# 7_ZynTra-DDR3L_Modules.net
KiCad netlist of a schematic drawn in Altium Designer
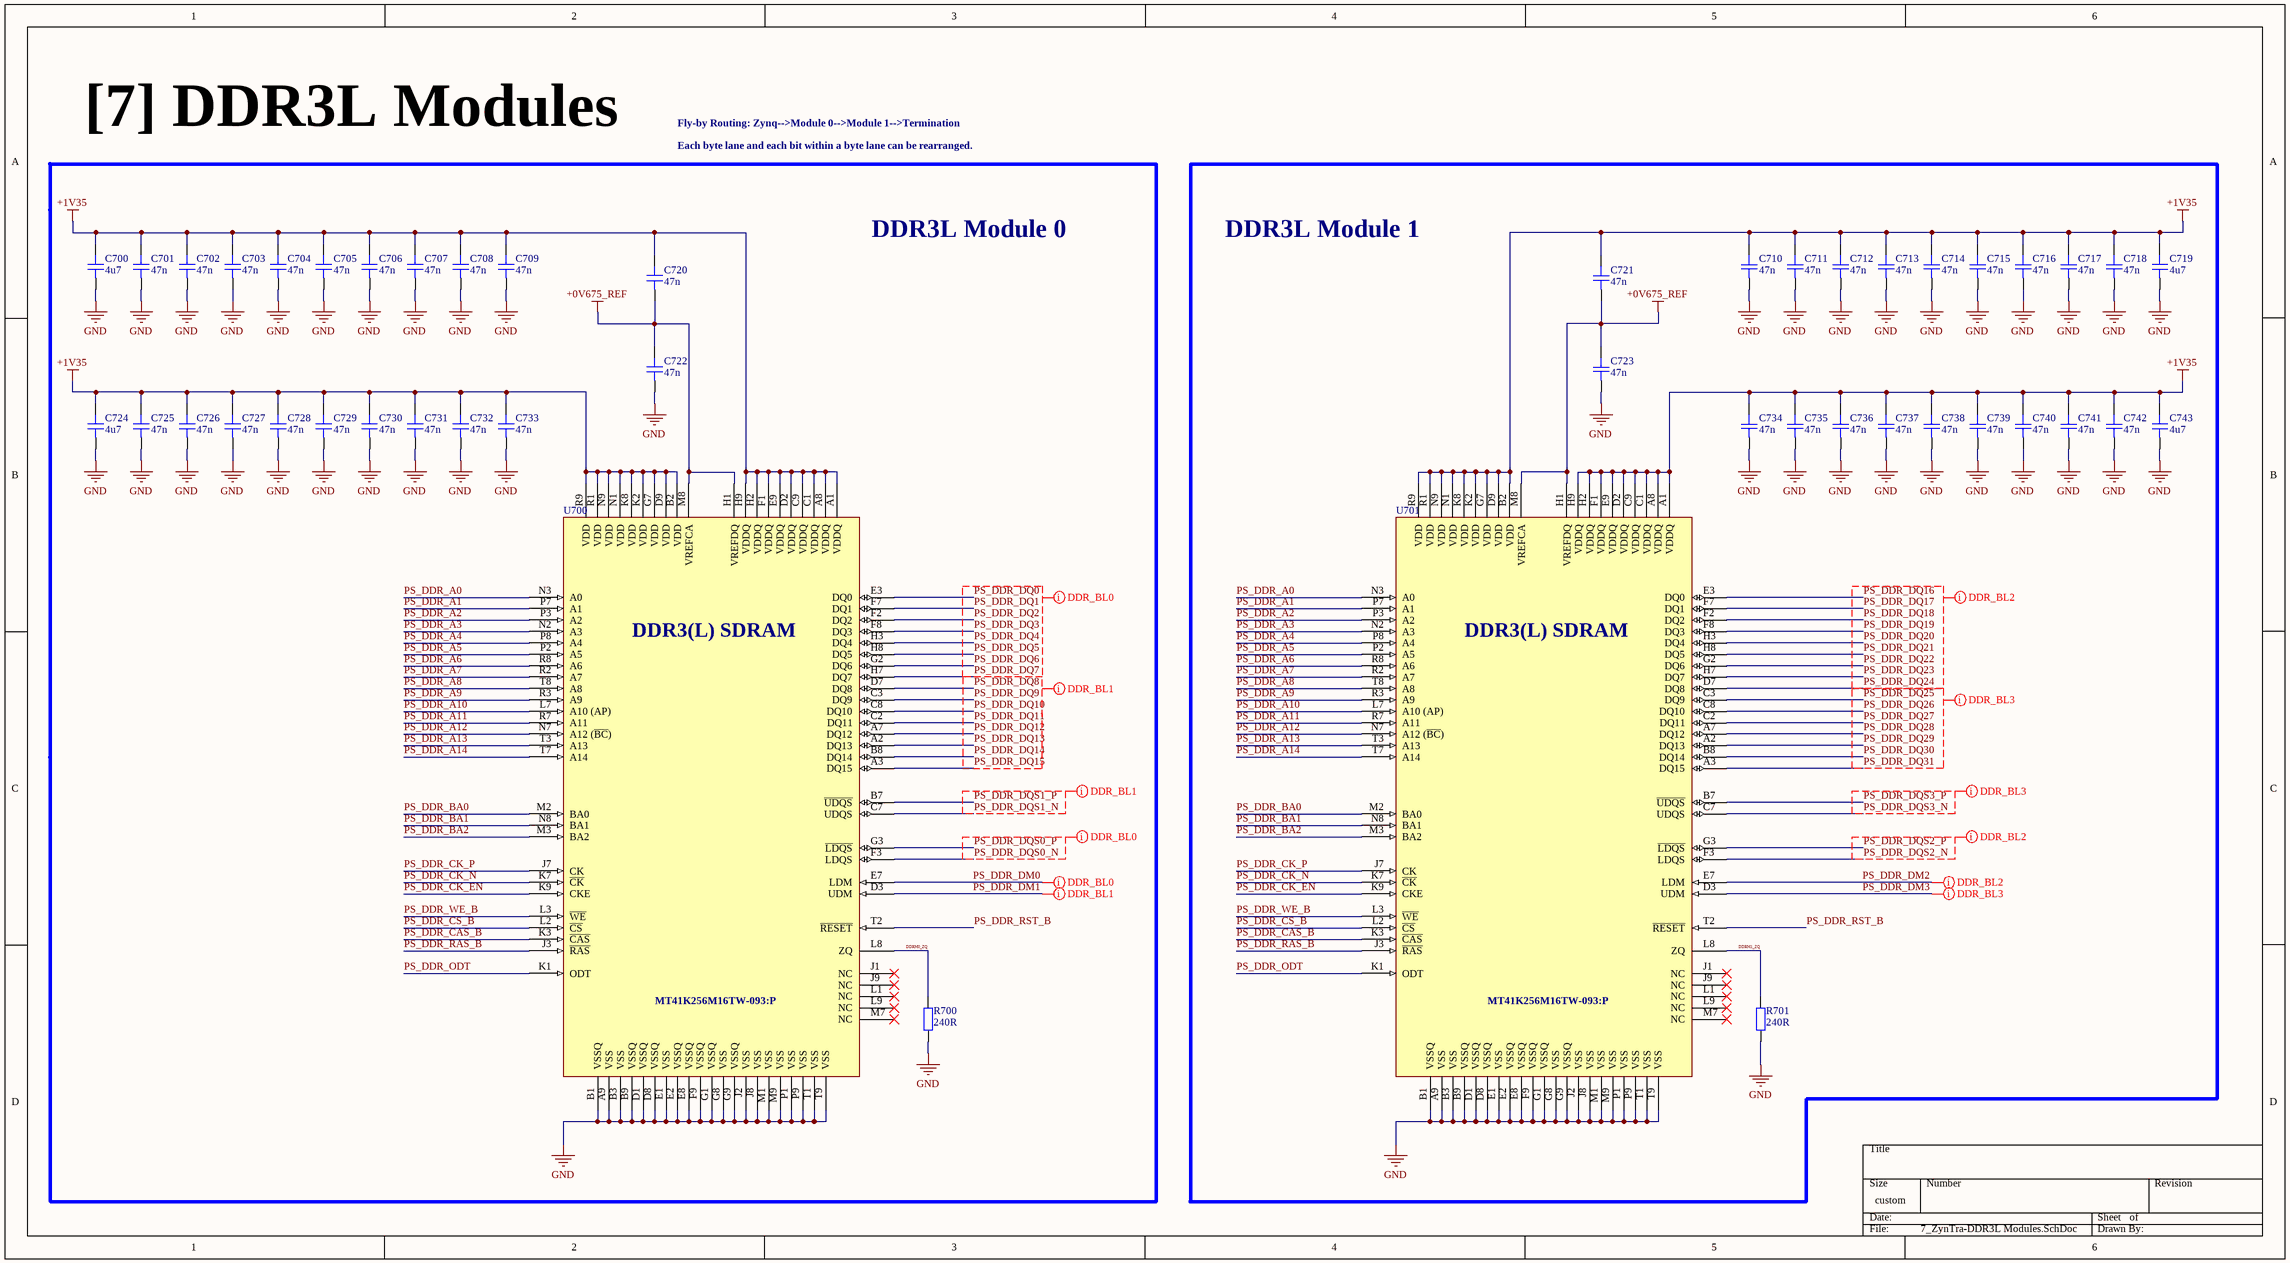
[diagram p0: 7_ZynTra-DDR3L Modules.SchDoc]

(export (version "E")
  (design (tool "Eeschema 10.0.6"))
  (components
    (comp (ref "C700")
      (value "4u7")
      (footprint "CAP_0402")
      (description "Capacitor SMD 0402")
      (libsource (lib "Schematic-Lib-PhilsLab") (part "CAP_0402"))
    )
    (comp (ref "C701")
      (value "47n")
      (footprint "CAP_0201")
      (description "Capacitor SMD 0201")
      (libsource (lib "Schematic-Lib-PhilsLab") (part "CAP_0201"))
    )
    (comp (ref "C702")
      (value "47n")
      (footprint "CAP_0201")
      (description "Capacitor SMD 0201")
      (libsource (lib "Schematic-Lib-PhilsLab") (part "CAP_0201"))
    )
    (comp (ref "C703")
      (value "47n")
      (footprint "CAP_0201")
      (description "Capacitor SMD 0201")
      (libsource (lib "Schematic-Lib-PhilsLab") (part "CAP_0201"))
    )
    (comp (ref "C704")
      (value "47n")
      (footprint "CAP_0201")
      (description "Capacitor SMD 0201")
      (libsource (lib "Schematic-Lib-PhilsLab") (part "CAP_0201"))
    )
    (comp (ref "C705")
      (value "47n")
      (footprint "CAP_0201")
      (description "Capacitor SMD 0201")
      (libsource (lib "Schematic-Lib-PhilsLab") (part "CAP_0201"))
    )
    (comp (ref "C706")
      (value "47n")
      (footprint "CAP_0201")
      (description "Capacitor SMD 0201")
      (libsource (lib "Schematic-Lib-PhilsLab") (part "CAP_0201"))
    )
    (comp (ref "C707")
      (value "47n")
      (footprint "CAP_0201")
      (description "Capacitor SMD 0201")
      (libsource (lib "Schematic-Lib-PhilsLab") (part "CAP_0201"))
    )
    (comp (ref "C708")
      (value "47n")
      (footprint "CAP_0201")
      (description "Capacitor SMD 0201")
      (libsource (lib "Schematic-Lib-PhilsLab") (part "CAP_0201"))
    )
    (comp (ref "C709")
      (value "47n")
      (footprint "CAP_0201")
      (description "Capacitor SMD 0201")
      (libsource (lib "Schematic-Lib-PhilsLab") (part "CAP_0201"))
    )
    (comp (ref "C710")
      (value "47n")
      (footprint "CAP_0201")
      (description "Capacitor SMD 0201")
      (libsource (lib "Schematic-Lib-PhilsLab") (part "CAP_0201"))
    )
    (comp (ref "C711")
      (value "47n")
      (footprint "CAP_0201")
      (description "Capacitor SMD 0201")
      (libsource (lib "Schematic-Lib-PhilsLab") (part "CAP_0201"))
    )
    (comp (ref "C712")
      (value "47n")
      (footprint "CAP_0201")
      (description "Capacitor SMD 0201")
      (libsource (lib "Schematic-Lib-PhilsLab") (part "CAP_0201"))
    )
    (comp (ref "C713")
      (value "47n")
      (footprint "CAP_0201")
      (description "Capacitor SMD 0201")
      (libsource (lib "Schematic-Lib-PhilsLab") (part "CAP_0201"))
    )
    (comp (ref "C714")
      (value "47n")
      (footprint "CAP_0201")
      (description "Capacitor SMD 0201")
      (libsource (lib "Schematic-Lib-PhilsLab") (part "CAP_0201"))
    )
    (comp (ref "C715")
      (value "47n")
      (footprint "CAP_0201")
      (description "Capacitor SMD 0201")
      (libsource (lib "Schematic-Lib-PhilsLab") (part "CAP_0201"))
    )
    (comp (ref "C716")
      (value "47n")
      (footprint "CAP_0201")
      (description "Capacitor SMD 0201")
      (libsource (lib "Schematic-Lib-PhilsLab") (part "CAP_0201"))
    )
    (comp (ref "C717")
      (value "47n")
      (footprint "CAP_0201")
      (description "Capacitor SMD 0201")
      (libsource (lib "Schematic-Lib-PhilsLab") (part "CAP_0201"))
    )
    (comp (ref "C718")
      (value "47n")
      (footprint "CAP_0201")
      (description "Capacitor SMD 0201")
      (libsource (lib "Schematic-Lib-PhilsLab") (part "CAP_0201"))
    )
    (comp (ref "C719")
      (value "4u7")
      (footprint "CAP_0402")
      (description "Capacitor SMD 0402")
      (libsource (lib "Schematic-Lib-PhilsLab") (part "CAP_0402"))
    )
    (comp (ref "C720")
      (value "47n")
      (footprint "CAP_0201")
      (description "Capacitor SMD 0201")
      (libsource (lib "Schematic-Lib-PhilsLab") (part "CAP_0201"))
    )
    (comp (ref "C721")
      (value "47n")
      (footprint "CAP_0201")
      (description "Capacitor SMD 0201")
      (libsource (lib "Schematic-Lib-PhilsLab") (part "CAP_0201"))
    )
    (comp (ref "C722")
      (value "47n")
      (footprint "CAP_0201")
      (description "Capacitor SMD 0201")
      (libsource (lib "Schematic-Lib-PhilsLab") (part "CAP_0201"))
    )
    (comp (ref "C723")
      (value "47n")
      (footprint "CAP_0201")
      (description "Capacitor SMD 0201")
      (libsource (lib "Schematic-Lib-PhilsLab") (part "CAP_0201"))
    )
    (comp (ref "C724")
      (value "4u7")
      (footprint "CAP_0402")
      (description "Capacitor SMD 0402")
      (libsource (lib "Schematic-Lib-PhilsLab") (part "CAP_0402"))
    )
    (comp (ref "C725")
      (value "47n")
      (footprint "CAP_0201")
      (description "Capacitor SMD 0201")
      (libsource (lib "Schematic-Lib-PhilsLab") (part "CAP_0201"))
    )
    (comp (ref "C726")
      (value "47n")
      (footprint "CAP_0201")
      (description "Capacitor SMD 0201")
      (libsource (lib "Schematic-Lib-PhilsLab") (part "CAP_0201"))
    )
    (comp (ref "C727")
      (value "47n")
      (footprint "CAP_0201")
      (description "Capacitor SMD 0201")
      (libsource (lib "Schematic-Lib-PhilsLab") (part "CAP_0201"))
    )
    (comp (ref "C728")
      (value "47n")
      (footprint "CAP_0201")
      (description "Capacitor SMD 0201")
      (libsource (lib "Schematic-Lib-PhilsLab") (part "CAP_0201"))
    )
    (comp (ref "C729")
      (value "47n")
      (footprint "CAP_0201")
      (description "Capacitor SMD 0201")
      (libsource (lib "Schematic-Lib-PhilsLab") (part "CAP_0201"))
    )
    (comp (ref "C730")
      (value "47n")
      (footprint "CAP_0201")
      (description "Capacitor SMD 0201")
      (libsource (lib "Schematic-Lib-PhilsLab") (part "CAP_0201"))
    )
    (comp (ref "C731")
      (value "47n")
      (footprint "CAP_0201")
      (description "Capacitor SMD 0201")
      (libsource (lib "Schematic-Lib-PhilsLab") (part "CAP_0201"))
    )
    (comp (ref "C732")
      (value "47n")
      (footprint "CAP_0201")
      (description "Capacitor SMD 0201")
      (libsource (lib "Schematic-Lib-PhilsLab") (part "CAP_0201"))
    )
    (comp (ref "C733")
      (value "47n")
      (footprint "CAP_0201")
      (description "Capacitor SMD 0201")
      (libsource (lib "Schematic-Lib-PhilsLab") (part "CAP_0201"))
    )
    (comp (ref "C734")
      (value "47n")
      (footprint "CAP_0201")
      (description "Capacitor SMD 0201")
      (libsource (lib "Schematic-Lib-PhilsLab") (part "CAP_0201"))
    )
    (comp (ref "C735")
      (value "47n")
      (footprint "CAP_0201")
      (description "Capacitor SMD 0201")
      (libsource (lib "Schematic-Lib-PhilsLab") (part "CAP_0201"))
    )
    (comp (ref "C736")
      (value "47n")
      (footprint "CAP_0201")
      (description "Capacitor SMD 0201")
      (libsource (lib "Schematic-Lib-PhilsLab") (part "CAP_0201"))
    )
    (comp (ref "C737")
      (value "47n")
      (footprint "CAP_0201")
      (description "Capacitor SMD 0201")
      (libsource (lib "Schematic-Lib-PhilsLab") (part "CAP_0201"))
    )
    (comp (ref "C738")
      (value "47n")
      (footprint "CAP_0201")
      (description "Capacitor SMD 0201")
      (libsource (lib "Schematic-Lib-PhilsLab") (part "CAP_0201"))
    )
    (comp (ref "C739")
      (value "47n")
      (footprint "CAP_0201")
      (description "Capacitor SMD 0201")
      (libsource (lib "Schematic-Lib-PhilsLab") (part "CAP_0201"))
    )
    (comp (ref "C740")
      (value "47n")
      (footprint "CAP_0201")
      (description "Capacitor SMD 0201")
      (libsource (lib "Schematic-Lib-PhilsLab") (part "CAP_0201"))
    )
    (comp (ref "C741")
      (value "47n")
      (footprint "CAP_0201")
      (description "Capacitor SMD 0201")
      (libsource (lib "Schematic-Lib-PhilsLab") (part "CAP_0201"))
    )
    (comp (ref "C742")
      (value "47n")
      (footprint "CAP_0201")
      (description "Capacitor SMD 0201")
      (libsource (lib "Schematic-Lib-PhilsLab") (part "CAP_0201"))
    )
    (comp (ref "C743")
      (value "4u7")
      (footprint "CAP_0402")
      (description "Capacitor SMD 0402")
      (libsource (lib "Schematic-Lib-PhilsLab") (part "CAP_0402"))
    )
    (comp (ref "R700")
      (value "240R")
      (footprint "RES_0201")
      (description "Resistor SMD 0201")
      (libsource (lib "Schematic-Lib-PhilsLab") (part "RES_0201"))
    )
    (comp (ref "R701")
      (value "240R")
      (footprint "RES_0201")
      (description "Resistor SMD 0201")
      (libsource (lib "Schematic-Lib-PhilsLab") (part "RES_0201"))
    )
    (comp (ref "U700")
      (value "MT41K256M16TW-093:P")
      (footprint "96-BALL, FBGA, 0.8mm")
      (description "DDR3L SDRAM")
      (fields (field (name "MANUFACTURER") "Micron Technology"))
      (libsource (lib "AtaSchLib") (part "MT41K256M16TW-093{colon}P"))
    )
    (comp (ref "U701")
      (value "MT41K256M16TW-093:P")
      (footprint "96-BALL, FBGA, 0.8mm")
      (description "DDR3L SDRAM")
      (fields (field (name "MANUFACTURER") "Micron Technology"))
      (libsource (lib "AtaSchLib") (part "MT41K256M16TW-093{colon}P"))
    )
  )
  (nets
    (net (code "1") (name "+0V675_REF") (class "Default")
      (node (ref "C720") (pin "1") (pinfunction "1_1") (pintype "passive"))
      (node (ref "C721") (pin "1") (pinfunction "1_1") (pintype "passive"))
      (node (ref "C722") (pin "2") (pinfunction "2_2") (pintype "passive"))
      (node (ref "C723") (pin "2") (pinfunction "2_2") (pintype "passive"))
      (node (ref "U700") (pin "H1") (pinfunction "VREFDQ_H1") (pintype "power_in"))
      (node (ref "U700") (pin "M8") (pinfunction "VREFCA_M8") (pintype "power_in"))
      (node (ref "U701") (pin "H1") (pinfunction "VREFDQ_H1") (pintype "power_in"))
      (node (ref "U701") (pin "M8") (pinfunction "VREFCA_M8") (pintype "power_in"))
    )
    (net (code "2") (name "+1V35") (class "Default")
      (node (ref "C700") (pin "2") (pinfunction "2_2") (pintype "passive"))
      (node (ref "C701") (pin "2") (pinfunction "2_2") (pintype "passive"))
      (node (ref "C702") (pin "2") (pinfunction "2_2") (pintype "passive"))
      (node (ref "C703") (pin "2") (pinfunction "2_2") (pintype "passive"))
      (node (ref "C704") (pin "2") (pinfunction "2_2") (pintype "passive"))
      (node (ref "C705") (pin "2") (pinfunction "2_2") (pintype "passive"))
      (node (ref "C706") (pin "2") (pinfunction "2_2") (pintype "passive"))
      (node (ref "C707") (pin "2") (pinfunction "2_2") (pintype "passive"))
      (node (ref "C708") (pin "2") (pinfunction "2_2") (pintype "passive"))
      (node (ref "C709") (pin "2") (pinfunction "2_2") (pintype "passive"))
      (node (ref "C710") (pin "2") (pinfunction "2_2") (pintype "passive"))
      (node (ref "C711") (pin "2") (pinfunction "2_2") (pintype "passive"))
      (node (ref "C712") (pin "2") (pinfunction "2_2") (pintype "passive"))
      (node (ref "C713") (pin "2") (pinfunction "2_2") (pintype "passive"))
      (node (ref "C714") (pin "2") (pinfunction "2_2") (pintype "passive"))
      (node (ref "C715") (pin "2") (pinfunction "2_2") (pintype "passive"))
      (node (ref "C716") (pin "2") (pinfunction "2_2") (pintype "passive"))
      (node (ref "C717") (pin "2") (pinfunction "2_2") (pintype "passive"))
      (node (ref "C718") (pin "2") (pinfunction "2_2") (pintype "passive"))
      (node (ref "C719") (pin "2") (pinfunction "2_2") (pintype "passive"))
      (node (ref "C720") (pin "2") (pinfunction "2_2") (pintype "passive"))
      (node (ref "C721") (pin "2") (pinfunction "2_2") (pintype "passive"))
      (node (ref "C724") (pin "2") (pinfunction "2_2") (pintype "passive"))
      (node (ref "C725") (pin "2") (pinfunction "2_2") (pintype "passive"))
      (node (ref "C726") (pin "2") (pinfunction "2_2") (pintype "passive"))
      (node (ref "C727") (pin "2") (pinfunction "2_2") (pintype "passive"))
      (node (ref "C728") (pin "2") (pinfunction "2_2") (pintype "passive"))
      (node (ref "C729") (pin "2") (pinfunction "2_2") (pintype "passive"))
      (node (ref "C730") (pin "2") (pinfunction "2_2") (pintype "passive"))
      (node (ref "C731") (pin "2") (pinfunction "2_2") (pintype "passive"))
      (node (ref "C732") (pin "2") (pinfunction "2_2") (pintype "passive"))
      (node (ref "C733") (pin "2") (pinfunction "2_2") (pintype "passive"))
      (node (ref "C734") (pin "2") (pinfunction "2_2") (pintype "passive"))
      (node (ref "C735") (pin "2") (pinfunction "2_2") (pintype "passive"))
      (node (ref "C736") (pin "2") (pinfunction "2_2") (pintype "passive"))
      (node (ref "C737") (pin "2") (pinfunction "2_2") (pintype "passive"))
      (node (ref "C738") (pin "2") (pinfunction "2_2") (pintype "passive"))
      (node (ref "C739") (pin "2") (pinfunction "2_2") (pintype "passive"))
      (node (ref "C740") (pin "2") (pinfunction "2_2") (pintype "passive"))
      (node (ref "C741") (pin "2") (pinfunction "2_2") (pintype "passive"))
      (node (ref "C742") (pin "2") (pinfunction "2_2") (pintype "passive"))
      (node (ref "C743") (pin "2") (pinfunction "2_2") (pintype "passive"))
      (node (ref "U700") (pin "A1") (pinfunction "VDDQ_A1") (pintype "power_in"))
      (node (ref "U700") (pin "A8") (pinfunction "VDDQ_A8") (pintype "power_in"))
      (node (ref "U700") (pin "B2") (pinfunction "VDD_B2") (pintype "power_in"))
      (node (ref "U700") (pin "C1") (pinfunction "VDDQ_C1") (pintype "power_in"))
      (node (ref "U700") (pin "C9") (pinfunction "VDDQ_C9") (pintype "power_in"))
      (node (ref "U700") (pin "D2") (pinfunction "VDDQ_D2") (pintype "power_in"))
      (node (ref "U700") (pin "D9") (pinfunction "VDD_D9") (pintype "power_in"))
      (node (ref "U700") (pin "E9") (pinfunction "VDDQ_E9") (pintype "power_in"))
      (node (ref "U700") (pin "F1") (pinfunction "VDDQ_F1") (pintype "power_in"))
      (node (ref "U700") (pin "G7") (pinfunction "VDD_G7") (pintype "power_in"))
      (node (ref "U700") (pin "H2") (pinfunction "VDDQ_H2") (pintype "power_in"))
      (node (ref "U700") (pin "H9") (pinfunction "VDDQ_H9") (pintype "power_in"))
      (node (ref "U700") (pin "K2") (pinfunction "VDD_K2") (pintype "power_in"))
      (node (ref "U700") (pin "K8") (pinfunction "VDD_K8") (pintype "power_in"))
      (node (ref "U700") (pin "N1") (pinfunction "VDD_N1") (pintype "power_in"))
      (node (ref "U700") (pin "N9") (pinfunction "VDD_N9") (pintype "power_in"))
      (node (ref "U700") (pin "R1") (pinfunction "VDD_R1") (pintype "power_in"))
      (node (ref "U700") (pin "R9") (pinfunction "VDD_R9") (pintype "power_in"))
      (node (ref "U701") (pin "A1") (pinfunction "VDDQ_A1") (pintype "power_in"))
      (node (ref "U701") (pin "A8") (pinfunction "VDDQ_A8") (pintype "power_in"))
      (node (ref "U701") (pin "B2") (pinfunction "VDD_B2") (pintype "power_in"))
      (node (ref "U701") (pin "C1") (pinfunction "VDDQ_C1") (pintype "power_in"))
      (node (ref "U701") (pin "C9") (pinfunction "VDDQ_C9") (pintype "power_in"))
      (node (ref "U701") (pin "D2") (pinfunction "VDDQ_D2") (pintype "power_in"))
      (node (ref "U701") (pin "D9") (pinfunction "VDD_D9") (pintype "power_in"))
      (node (ref "U701") (pin "E9") (pinfunction "VDDQ_E9") (pintype "power_in"))
      (node (ref "U701") (pin "F1") (pinfunction "VDDQ_F1") (pintype "power_in"))
      (node (ref "U701") (pin "G7") (pinfunction "VDD_G7") (pintype "power_in"))
      (node (ref "U701") (pin "H2") (pinfunction "VDDQ_H2") (pintype "power_in"))
      (node (ref "U701") (pin "H9") (pinfunction "VDDQ_H9") (pintype "power_in"))
      (node (ref "U701") (pin "K2") (pinfunction "VDD_K2") (pintype "power_in"))
      (node (ref "U701") (pin "K8") (pinfunction "VDD_K8") (pintype "power_in"))
      (node (ref "U701") (pin "N1") (pinfunction "VDD_N1") (pintype "power_in"))
      (node (ref "U701") (pin "N9") (pinfunction "VDD_N9") (pintype "power_in"))
      (node (ref "U701") (pin "R1") (pinfunction "VDD_R1") (pintype "power_in"))
      (node (ref "U701") (pin "R9") (pinfunction "VDD_R9") (pintype "power_in"))
    )
    (net (code "3") (name "/DDRM0_ZQ") (class "Default")
      (node (ref "R700") (pin "2") (pinfunction "2_2") (pintype "passive"))
      (node (ref "U700") (pin "L8") (pinfunction "ZQ_L8") (pintype "power_in"))
    )
    (net (code "4") (name "/DDRM1_ZQ") (class "Default")
      (node (ref "R701") (pin "2") (pinfunction "2_2") (pintype "passive"))
      (node (ref "U701") (pin "L8") (pinfunction "ZQ_L8") (pintype "power_in"))
    )
    (net (code "5") (name "/PS_DDR_A0") (class "Default")
      (node (ref "U700") (pin "N3") (pinfunction "A0_N3") (pintype "input"))
      (node (ref "U701") (pin "N3") (pinfunction "A0_N3") (pintype "input"))
    )
    (net (code "6") (name "/PS_DDR_A1") (class "Default")
      (node (ref "U700") (pin "P7") (pinfunction "A1_P7") (pintype "input"))
      (node (ref "U701") (pin "P7") (pinfunction "A1_P7") (pintype "input"))
    )
    (net (code "7") (name "/PS_DDR_A2") (class "Default")
      (node (ref "U700") (pin "P3") (pinfunction "A2_P3") (pintype "input"))
      (node (ref "U701") (pin "P3") (pinfunction "A2_P3") (pintype "input"))
    )
    (net (code "8") (name "/PS_DDR_A3") (class "Default")
      (node (ref "U700") (pin "N2") (pinfunction "A3_N2") (pintype "input"))
      (node (ref "U701") (pin "N2") (pinfunction "A3_N2") (pintype "input"))
    )
    (net (code "9") (name "/PS_DDR_A4") (class "Default")
      (node (ref "U700") (pin "P8") (pinfunction "A4_P8") (pintype "input"))
      (node (ref "U701") (pin "P8") (pinfunction "A4_P8") (pintype "input"))
    )
    (net (code "10") (name "/PS_DDR_A5") (class "Default")
      (node (ref "U700") (pin "P2") (pinfunction "A5_P2") (pintype "input"))
      (node (ref "U701") (pin "P2") (pinfunction "A5_P2") (pintype "input"))
    )
    (net (code "11") (name "/PS_DDR_A6") (class "Default")
      (node (ref "U700") (pin "R8") (pinfunction "A6_R8") (pintype "input"))
      (node (ref "U701") (pin "R8") (pinfunction "A6_R8") (pintype "input"))
    )
    (net (code "12") (name "/PS_DDR_A7") (class "Default")
      (node (ref "U700") (pin "R2") (pinfunction "A7_R2") (pintype "input"))
      (node (ref "U701") (pin "R2") (pinfunction "A7_R2") (pintype "input"))
    )
    (net (code "13") (name "/PS_DDR_A8") (class "Default")
      (node (ref "U700") (pin "T8") (pinfunction "A8_T8") (pintype "input"))
      (node (ref "U701") (pin "T8") (pinfunction "A8_T8") (pintype "input"))
    )
    (net (code "14") (name "/PS_DDR_A9") (class "Default")
      (node (ref "U700") (pin "R3") (pinfunction "A9_R3") (pintype "input"))
      (node (ref "U701") (pin "R3") (pinfunction "A9_R3") (pintype "input"))
    )
    (net (code "15") (name "/PS_DDR_A10") (class "Default")
      (node (ref "U700") (pin "L7") (pinfunction "A10_(AP)_L7") (pintype "input"))
      (node (ref "U701") (pin "L7") (pinfunction "A10_(AP)_L7") (pintype "input"))
    )
    (net (code "16") (name "/PS_DDR_A11") (class "Default")
      (node (ref "U700") (pin "R7") (pinfunction "A11_R7") (pintype "input"))
      (node (ref "U701") (pin "R7") (pinfunction "A11_R7") (pintype "input"))
    )
    (net (code "17") (name "/PS_DDR_A12") (class "Default")
      (node (ref "U700") (pin "N7") (pinfunction "A12_(~{BC})_N7") (pintype "input"))
      (node (ref "U701") (pin "N7") (pinfunction "A12_(~{BC})_N7") (pintype "input"))
    )
    (net (code "18") (name "/PS_DDR_A13") (class "Default")
      (node (ref "U700") (pin "T3") (pinfunction "A13_T3") (pintype "input"))
      (node (ref "U701") (pin "T3") (pinfunction "A13_T3") (pintype "input"))
    )
    (net (code "19") (name "/PS_DDR_A14") (class "Default")
      (node (ref "U700") (pin "T7") (pinfunction "A14_T7") (pintype "input"))
      (node (ref "U701") (pin "T7") (pinfunction "A14_T7") (pintype "input"))
    )
    (net (code "20") (name "/PS_DDR_BA0") (class "Default")
      (node (ref "U700") (pin "M2") (pinfunction "BA0_M2") (pintype "input"))
      (node (ref "U701") (pin "M2") (pinfunction "BA0_M2") (pintype "input"))
    )
    (net (code "21") (name "/PS_DDR_BA1") (class "Default")
      (node (ref "U700") (pin "N8") (pinfunction "BA1_N8") (pintype "input"))
      (node (ref "U701") (pin "N8") (pinfunction "BA1_N8") (pintype "input"))
    )
    (net (code "22") (name "/PS_DDR_BA2") (class "Default")
      (node (ref "U700") (pin "M3") (pinfunction "BA2_M3") (pintype "input"))
      (node (ref "U701") (pin "M3") (pinfunction "BA2_M3") (pintype "input"))
    )
    (net (code "23") (name "/PS_DDR_CAS_B") (class "Default")
      (node (ref "U700") (pin "K3") (pinfunction "~{CAS}_K3") (pintype "input"))
      (node (ref "U701") (pin "K3") (pinfunction "~{CAS}_K3") (pintype "input"))
    )
    (net (code "24") (name "/PS_DDR_CK_EN") (class "Default")
      (node (ref "U700") (pin "K9") (pinfunction "CKE_K9") (pintype "input"))
      (node (ref "U701") (pin "K9") (pinfunction "CKE_K9") (pintype "input"))
    )
    (net (code "25") (name "/PS_DDR_CK_N") (class "Default")
      (node (ref "U700") (pin "K7") (pinfunction "~{CK}_K7") (pintype "input"))
      (node (ref "U701") (pin "K7") (pinfunction "~{CK}_K7") (pintype "input"))
    )
    (net (code "26") (name "/PS_DDR_CK_P") (class "Default")
      (node (ref "U700") (pin "J7") (pinfunction "CK_J7") (pintype "input"))
      (node (ref "U701") (pin "J7") (pinfunction "CK_J7") (pintype "input"))
    )
    (net (code "27") (name "/PS_DDR_CS_B") (class "Default")
      (node (ref "U700") (pin "L2") (pinfunction "~{CS}_L2") (pintype "input"))
      (node (ref "U701") (pin "L2") (pinfunction "~{CS}_L2") (pintype "input"))
    )
    (net (code "28") (name "/PS_DDR_DM0") (class "Default")
      (node (ref "U700") (pin "E7") (pinfunction "LDM_E7") (pintype "input"))
    )
    (net (code "29") (name "/PS_DDR_DM1") (class "Default")
      (node (ref "U700") (pin "D3") (pinfunction "UDM_D3") (pintype "input"))
    )
    (net (code "30") (name "/PS_DDR_DM2") (class "Default")
      (node (ref "U701") (pin "E7") (pinfunction "LDM_E7") (pintype "input"))
    )
    (net (code "31") (name "/PS_DDR_DM3") (class "Default")
      (node (ref "U701") (pin "D3") (pinfunction "UDM_D3") (pintype "input"))
    )
    (net (code "32") (name "/PS_DDR_DQ0") (class "Default")
      (node (ref "U700") (pin "E3") (pinfunction "DQ0_E3") (pintype "bidirectional"))
    )
    (net (code "33") (name "/PS_DDR_DQ1") (class "Default")
      (node (ref "U700") (pin "F7") (pinfunction "DQ1_F7") (pintype "bidirectional"))
    )
    (net (code "34") (name "/PS_DDR_DQ2") (class "Default")
      (node (ref "U700") (pin "F2") (pinfunction "DQ2_F2") (pintype "bidirectional"))
    )
    (net (code "35") (name "/PS_DDR_DQ3") (class "Default")
      (node (ref "U700") (pin "F8") (pinfunction "DQ3_F8") (pintype "bidirectional"))
    )
    (net (code "36") (name "/PS_DDR_DQ4") (class "Default")
      (node (ref "U700") (pin "H3") (pinfunction "DQ4_H3") (pintype "bidirectional"))
    )
    (net (code "37") (name "/PS_DDR_DQ5") (class "Default")
      (node (ref "U700") (pin "H8") (pinfunction "DQ5_H8") (pintype "bidirectional"))
    )
    (net (code "38") (name "/PS_DDR_DQ6") (class "Default")
      (node (ref "U700") (pin "G2") (pinfunction "DQ6_G2") (pintype "bidirectional"))
    )
    (net (code "39") (name "/PS_DDR_DQ7") (class "Default")
      (node (ref "U700") (pin "H7") (pinfunction "DQ7_H7") (pintype "bidirectional"))
    )
    (net (code "40") (name "/PS_DDR_DQ8") (class "Default")
      (node (ref "U700") (pin "D7") (pinfunction "DQ8_D7") (pintype "bidirectional"))
    )
    (net (code "41") (name "/PS_DDR_DQ9") (class "Default")
      (node (ref "U700") (pin "C3") (pinfunction "DQ9_C3") (pintype "bidirectional"))
    )
    (net (code "42") (name "/PS_DDR_DQ10") (class "Default")
      (node (ref "U700") (pin "C8") (pinfunction "DQ10_C8") (pintype "bidirectional"))
    )
    (net (code "43") (name "/PS_DDR_DQ11") (class "Default")
      (node (ref "U700") (pin "C2") (pinfunction "DQ11_C2") (pintype "bidirectional"))
    )
    (net (code "44") (name "/PS_DDR_DQ12") (class "Default")
      (node (ref "U700") (pin "A7") (pinfunction "DQ12_A7") (pintype "bidirectional"))
    )
    (net (code "45") (name "/PS_DDR_DQ13") (class "Default")
      (node (ref "U700") (pin "A2") (pinfunction "DQ13_A2") (pintype "bidirectional"))
    )
    (net (code "46") (name "/PS_DDR_DQ14") (class "Default")
      (node (ref "U700") (pin "B8") (pinfunction "DQ14_B8") (pintype "bidirectional"))
    )
    (net (code "47") (name "/PS_DDR_DQ15") (class "Default")
      (node (ref "U700") (pin "A3") (pinfunction "DQ15_A3") (pintype "bidirectional"))
    )
    (net (code "48") (name "/PS_DDR_DQ16") (class "Default")
      (node (ref "U701") (pin "E3") (pinfunction "DQ0_E3") (pintype "bidirectional"))
    )
    (net (code "49") (name "/PS_DDR_DQ17") (class "Default")
      (node (ref "U701") (pin "F7") (pinfunction "DQ1_F7") (pintype "bidirectional"))
    )
    (net (code "50") (name "/PS_DDR_DQ18") (class "Default")
      (node (ref "U701") (pin "F2") (pinfunction "DQ2_F2") (pintype "bidirectional"))
    )
    (net (code "51") (name "/PS_DDR_DQ19") (class "Default")
      (node (ref "U701") (pin "F8") (pinfunction "DQ3_F8") (pintype "bidirectional"))
    )
    (net (code "52") (name "/PS_DDR_DQ20") (class "Default")
      (node (ref "U701") (pin "H3") (pinfunction "DQ4_H3") (pintype "bidirectional"))
    )
    (net (code "53") (name "/PS_DDR_DQ21") (class "Default")
      (node (ref "U701") (pin "H8") (pinfunction "DQ5_H8") (pintype "bidirectional"))
    )
    (net (code "54") (name "/PS_DDR_DQ22") (class "Default")
      (node (ref "U701") (pin "G2") (pinfunction "DQ6_G2") (pintype "bidirectional"))
    )
    (net (code "55") (name "/PS_DDR_DQ23") (class "Default")
      (node (ref "U701") (pin "H7") (pinfunction "DQ7_H7") (pintype "bidirectional"))
    )
    (net (code "56") (name "/PS_DDR_DQ24") (class "Default")
      (node (ref "U701") (pin "D7") (pinfunction "DQ8_D7") (pintype "bidirectional"))
    )
    (net (code "57") (name "/PS_DDR_DQ25") (class "Default")
      (node (ref "U701") (pin "C3") (pinfunction "DQ9_C3") (pintype "bidirectional"))
    )
    (net (code "58") (name "/PS_DDR_DQ26") (class "Default")
      (node (ref "U701") (pin "C8") (pinfunction "DQ10_C8") (pintype "bidirectional"))
    )
    (net (code "59") (name "/PS_DDR_DQ27") (class "Default")
      (node (ref "U701") (pin "C2") (pinfunction "DQ11_C2") (pintype "bidirectional"))
    )
    (net (code "60") (name "/PS_DDR_DQ28") (class "Default")
      (node (ref "U701") (pin "A7") (pinfunction "DQ12_A7") (pintype "bidirectional"))
    )
    (net (code "61") (name "/PS_DDR_DQ29") (class "Default")
      (node (ref "U701") (pin "A2") (pinfunction "DQ13_A2") (pintype "bidirectional"))
    )
    (net (code "62") (name "/PS_DDR_DQ30") (class "Default")
      (node (ref "U701") (pin "B8") (pinfunction "DQ14_B8") (pintype "bidirectional"))
    )
    (net (code "63") (name "/PS_DDR_DQ31") (class "Default")
      (node (ref "U701") (pin "A3") (pinfunction "DQ15_A3") (pintype "bidirectional"))
    )
    (net (code "64") (name "/PS_DDR_DQS0_N") (class "Default")
      (node (ref "U700") (pin "F3") (pinfunction "LDQS_F3") (pintype "bidirectional"))
    )
    (net (code "65") (name "/PS_DDR_DQS0_P") (class "Default")
      (node (ref "U700") (pin "G3") (pinfunction "~{LDQS}_G3") (pintype "bidirectional"))
    )
    (net (code "66") (name "/PS_DDR_DQS1_N") (class "Default")
      (node (ref "U700") (pin "C7") (pinfunction "UDQS_C7") (pintype "bidirectional"))
    )
    (net (code "67") (name "/PS_DDR_DQS1_P") (class "Default")
      (node (ref "U700") (pin "B7") (pinfunction "~{UDQS}_B7") (pintype "bidirectional"))
    )
    (net (code "68") (name "/PS_DDR_DQS2_N") (class "Default")
      (node (ref "U701") (pin "F3") (pinfunction "LDQS_F3") (pintype "bidirectional"))
    )
    (net (code "69") (name "/PS_DDR_DQS2_P") (class "Default")
      (node (ref "U701") (pin "G3") (pinfunction "~{LDQS}_G3") (pintype "bidirectional"))
    )
    (net (code "70") (name "/PS_DDR_DQS3_N") (class "Default")
      (node (ref "U701") (pin "C7") (pinfunction "UDQS_C7") (pintype "bidirectional"))
    )
    (net (code "71") (name "/PS_DDR_DQS3_P") (class "Default")
      (node (ref "U701") (pin "B7") (pinfunction "~{UDQS}_B7") (pintype "bidirectional"))
    )
    (net (code "72") (name "/PS_DDR_ODT") (class "Default")
      (node (ref "U700") (pin "K1") (pinfunction "ODT_K1") (pintype "input"))
      (node (ref "U701") (pin "K1") (pinfunction "ODT_K1") (pintype "input"))
    )
    (net (code "73") (name "/PS_DDR_RAS_B") (class "Default")
      (node (ref "U700") (pin "J3") (pinfunction "~{RAS}_J3") (pintype "input"))
      (node (ref "U701") (pin "J3") (pinfunction "~{RAS}_J3") (pintype "input"))
    )
    (net (code "74") (name "/PS_DDR_RST_B") (class "Default")
      (node (ref "U700") (pin "T2") (pinfunction "~{RESET}_T2") (pintype "input"))
      (node (ref "U701") (pin "T2") (pinfunction "~{RESET}_T2") (pintype "input"))
    )
    (net (code "75") (name "/PS_DDR_WE_B") (class "Default")
      (node (ref "U700") (pin "L3") (pinfunction "~{WE}_L3") (pintype "input"))
      (node (ref "U701") (pin "L3") (pinfunction "~{WE}_L3") (pintype "input"))
    )
    (net (code "76") (name "GND") (class "Default")
      (node (ref "C700") (pin "1") (pinfunction "1_1") (pintype "passive"))
      (node (ref "C701") (pin "1") (pinfunction "1_1") (pintype "passive"))
      (node (ref "C702") (pin "1") (pinfunction "1_1") (pintype "passive"))
      (node (ref "C703") (pin "1") (pinfunction "1_1") (pintype "passive"))
      (node (ref "C704") (pin "1") (pinfunction "1_1") (pintype "passive"))
      (node (ref "C705") (pin "1") (pinfunction "1_1") (pintype "passive"))
      (node (ref "C706") (pin "1") (pinfunction "1_1") (pintype "passive"))
      (node (ref "C707") (pin "1") (pinfunction "1_1") (pintype "passive"))
      (node (ref "C708") (pin "1") (pinfunction "1_1") (pintype "passive"))
      (node (ref "C709") (pin "1") (pinfunction "1_1") (pintype "passive"))
      (node (ref "C710") (pin "1") (pinfunction "1_1") (pintype "passive"))
      (node (ref "C711") (pin "1") (pinfunction "1_1") (pintype "passive"))
      (node (ref "C712") (pin "1") (pinfunction "1_1") (pintype "passive"))
      (node (ref "C713") (pin "1") (pinfunction "1_1") (pintype "passive"))
      (node (ref "C714") (pin "1") (pinfunction "1_1") (pintype "passive"))
      (node (ref "C715") (pin "1") (pinfunction "1_1") (pintype "passive"))
      (node (ref "C716") (pin "1") (pinfunction "1_1") (pintype "passive"))
      (node (ref "C717") (pin "1") (pinfunction "1_1") (pintype "passive"))
      (node (ref "C718") (pin "1") (pinfunction "1_1") (pintype "passive"))
      (node (ref "C719") (pin "1") (pinfunction "1_1") (pintype "passive"))
      (node (ref "C722") (pin "1") (pinfunction "1_1") (pintype "passive"))
      (node (ref "C723") (pin "1") (pinfunction "1_1") (pintype "passive"))
      (node (ref "C724") (pin "1") (pinfunction "1_1") (pintype "passive"))
      (node (ref "C725") (pin "1") (pinfunction "1_1") (pintype "passive"))
      (node (ref "C726") (pin "1") (pinfunction "1_1") (pintype "passive"))
      (node (ref "C727") (pin "1") (pinfunction "1_1") (pintype "passive"))
      (node (ref "C728") (pin "1") (pinfunction "1_1") (pintype "passive"))
      (node (ref "C729") (pin "1") (pinfunction "1_1") (pintype "passive"))
      (node (ref "C730") (pin "1") (pinfunction "1_1") (pintype "passive"))
      (node (ref "C731") (pin "1") (pinfunction "1_1") (pintype "passive"))
      (node (ref "C732") (pin "1") (pinfunction "1_1") (pintype "passive"))
      (node (ref "C733") (pin "1") (pinfunction "1_1") (pintype "passive"))
      (node (ref "C734") (pin "1") (pinfunction "1_1") (pintype "passive"))
      (node (ref "C735") (pin "1") (pinfunction "1_1") (pintype "passive"))
      (node (ref "C736") (pin "1") (pinfunction "1_1") (pintype "passive"))
      (node (ref "C737") (pin "1") (pinfunction "1_1") (pintype "passive"))
      (node (ref "C738") (pin "1") (pinfunction "1_1") (pintype "passive"))
      (node (ref "C739") (pin "1") (pinfunction "1_1") (pintype "passive"))
      (node (ref "C740") (pin "1") (pinfunction "1_1") (pintype "passive"))
      (node (ref "C741") (pin "1") (pinfunction "1_1") (pintype "passive"))
      (node (ref "C742") (pin "1") (pinfunction "1_1") (pintype "passive"))
      (node (ref "C743") (pin "1") (pinfunction "1_1") (pintype "passive"))
      (node (ref "R700") (pin "1") (pinfunction "1_1") (pintype "passive"))
      (node (ref "R701") (pin "1") (pinfunction "1_1") (pintype "passive"))
      (node (ref "U700") (pin "A9") (pinfunction "VSS_A9") (pintype "power_in"))
      (node (ref "U700") (pin "B1") (pinfunction "VSSQ_B1") (pintype "power_in"))
      (node (ref "U700") (pin "B3") (pinfunction "VSS_B3") (pintype "power_in"))
      (node (ref "U700") (pin "B9") (pinfunction "VSSQ_B9") (pintype "power_in"))
      (node (ref "U700") (pin "D1") (pinfunction "VSSQ_D1") (pintype "power_in"))
      (node (ref "U700") (pin "D8") (pinfunction "VSSQ_D8") (pintype "power_in"))
      (node (ref "U700") (pin "E1") (pinfunction "VSS_E1") (pintype "power_in"))
      (node (ref "U700") (pin "E2") (pinfunction "VSSQ_E2") (pintype "power_in"))
      (node (ref "U700") (pin "E8") (pinfunction "VSSQ_E8") (pintype "power_in"))
      (node (ref "U700") (pin "F9") (pinfunction "VSSQ_F9") (pintype "power_in"))
      (node (ref "U700") (pin "G1") (pinfunction "VSSQ_G1") (pintype "power_in"))
      (node (ref "U700") (pin "G8") (pinfunction "VSS_G8") (pintype "power_in"))
      (node (ref "U700") (pin "G9") (pinfunction "VSSQ_G9") (pintype "power_in"))
      (node (ref "U700") (pin "J2") (pinfunction "VSS_J2") (pintype "power_in"))
      (node (ref "U700") (pin "J8") (pinfunction "VSS_J8") (pintype "power_in"))
      (node (ref "U700") (pin "M1") (pinfunction "VSS_M1") (pintype "power_in"))
      (node (ref "U700") (pin "M9") (pinfunction "VSS_M9") (pintype "power_in"))
      (node (ref "U700") (pin "P1") (pinfunction "VSS_P1") (pintype "power_in"))
      (node (ref "U700") (pin "P9") (pinfunction "VSS_P9") (pintype "power_in"))
      (node (ref "U700") (pin "T1") (pinfunction "VSS_T1") (pintype "power_in"))
      (node (ref "U700") (pin "T9") (pinfunction "VSS_T9") (pintype "power_in"))
      (node (ref "U701") (pin "A9") (pinfunction "VSS_A9") (pintype "power_in"))
      (node (ref "U701") (pin "B1") (pinfunction "VSSQ_B1") (pintype "power_in"))
      (node (ref "U701") (pin "B3") (pinfunction "VSS_B3") (pintype "power_in"))
      (node (ref "U701") (pin "B9") (pinfunction "VSSQ_B9") (pintype "power_in"))
      (node (ref "U701") (pin "D1") (pinfunction "VSSQ_D1") (pintype "power_in"))
      (node (ref "U701") (pin "D8") (pinfunction "VSSQ_D8") (pintype "power_in"))
      (node (ref "U701") (pin "E1") (pinfunction "VSS_E1") (pintype "power_in"))
      (node (ref "U701") (pin "E2") (pinfunction "VSSQ_E2") (pintype "power_in"))
      (node (ref "U701") (pin "E8") (pinfunction "VSSQ_E8") (pintype "power_in"))
      (node (ref "U701") (pin "F9") (pinfunction "VSSQ_F9") (pintype "power_in"))
      (node (ref "U701") (pin "G1") (pinfunction "VSSQ_G1") (pintype "power_in"))
      (node (ref "U701") (pin "G8") (pinfunction "VSS_G8") (pintype "power_in"))
      (node (ref "U701") (pin "G9") (pinfunction "VSSQ_G9") (pintype "power_in"))
      (node (ref "U701") (pin "J2") (pinfunction "VSS_J2") (pintype "power_in"))
      (node (ref "U701") (pin "J8") (pinfunction "VSS_J8") (pintype "power_in"))
      (node (ref "U701") (pin "M1") (pinfunction "VSS_M1") (pintype "power_in"))
      (node (ref "U701") (pin "M9") (pinfunction "VSS_M9") (pintype "power_in"))
      (node (ref "U701") (pin "P1") (pinfunction "VSS_P1") (pintype "power_in"))
      (node (ref "U701") (pin "P9") (pinfunction "VSS_P9") (pintype "power_in"))
      (node (ref "U701") (pin "T1") (pinfunction "VSS_T1") (pintype "power_in"))
      (node (ref "U701") (pin "T9") (pinfunction "VSS_T9") (pintype "power_in"))
    )
    (net (code "77") (name "unconnected-(U700-NC-PadJ1)") (class "Default")
      (node (ref "U700") (pin "J1") (pinfunction "NC_J1") (pintype "power_in+no_connect"))
    )
    (net (code "78") (name "unconnected-(U700-NC-PadJ9)") (class "Default")
      (node (ref "U700") (pin "J9") (pinfunction "NC_J9") (pintype "power_in+no_connect"))
    )
    (net (code "79") (name "unconnected-(U700-NC-PadL1)") (class "Default")
      (node (ref "U700") (pin "L1") (pinfunction "NC_L1") (pintype "power_in+no_connect"))
    )
    (net (code "80") (name "unconnected-(U700-NC-PadL9)") (class "Default")
      (node (ref "U700") (pin "L9") (pinfunction "NC_L9") (pintype "power_in+no_connect"))
    )
    (net (code "81") (name "unconnected-(U700-NC-PadM7)") (class "Default")
      (node (ref "U700") (pin "M7") (pinfunction "NC_M7") (pintype "power_in+no_connect"))
    )
    (net (code "82") (name "unconnected-(U701-NC-PadJ1)") (class "Default")
      (node (ref "U701") (pin "J1") (pinfunction "NC_J1") (pintype "power_in+no_connect"))
    )
    (net (code "83") (name "unconnected-(U701-NC-PadJ9)") (class "Default")
      (node (ref "U701") (pin "J9") (pinfunction "NC_J9") (pintype "power_in+no_connect"))
    )
    (net (code "84") (name "unconnected-(U701-NC-PadL1)") (class "Default")
      (node (ref "U701") (pin "L1") (pinfunction "NC_L1") (pintype "power_in+no_connect"))
    )
    (net (code "85") (name "unconnected-(U701-NC-PadL9)") (class "Default")
      (node (ref "U701") (pin "L9") (pinfunction "NC_L9") (pintype "power_in+no_connect"))
    )
    (net (code "86") (name "unconnected-(U701-NC-PadM7)") (class "Default")
      (node (ref "U701") (pin "M7") (pinfunction "NC_M7") (pintype "power_in+no_connect"))
    )
  )
)
